# STM32.net
KiCad netlist of a schematic drawn in Altium Designer
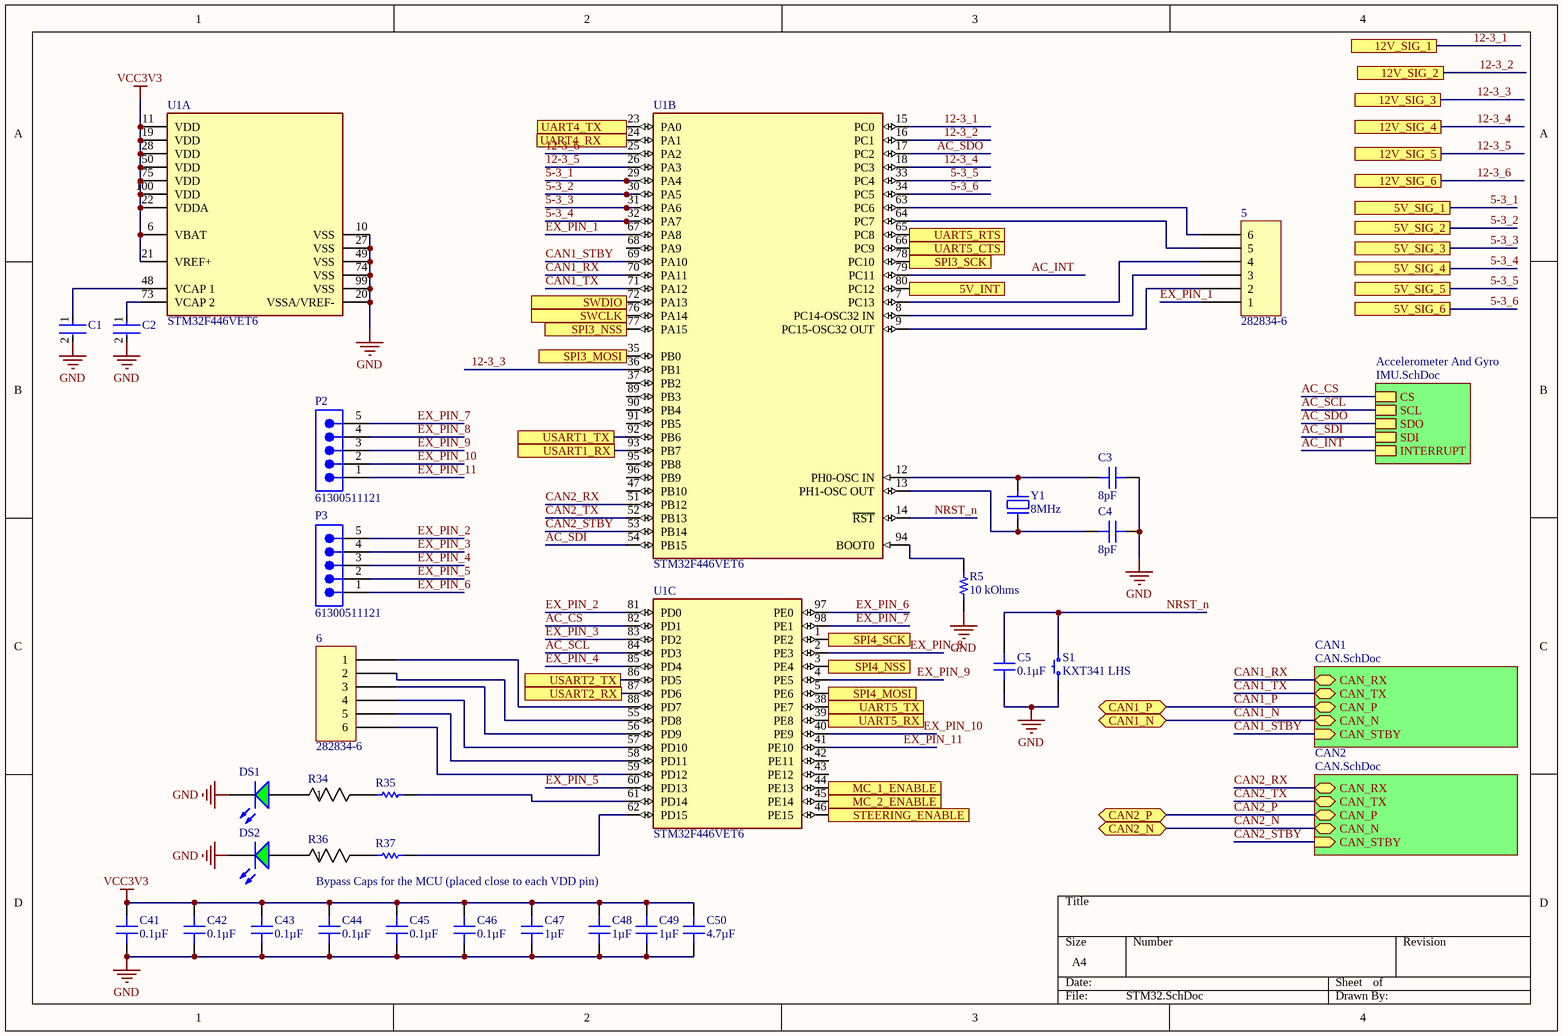
[diagram p0: STM32.SchDoc]

(export (version "E")
  (design (tool "Eeschema 10.0.6"))
  (components
    (comp (ref "5")
      (value "282834-6")
      (footprint "TE 282834-6")
      (description "TERM BLK 6P SIDE ENT 2.54MM PCB")
      (fields (field (name "MANUFACTURER") "TE Connectivity AMP Connectors") (field (name "VOLTAGE") "150V"))
      (libsource (lib "") (part "6 Pin_1"))
    )
    (comp (ref "6")
      (value "282834-6")
      (footprint "TE 282834-6")
      (description "TERM BLK 6P SIDE ENT 2.54MM PCB")
      (fields (field (name "MANUFACTURER") "TE Connectivity AMP Connectors") (field (name "VOLTAGE") "150V"))
      (libsource (lib "Celestial Altium Library - altium_library") (part "6 Pin"))
    )
    (comp (ref "C1")
      (value "GRM188R71A225KE15D")
      (footprint "FP-GRM188-0_1-e0_2_0_5-MFG")
      (description "Chip Multilayer Ceramic Capacitors for General Purpose, 0603, 2.2uF, X7R, 15%, 10%, 10V")
      (fields (field (name "VOLTAGE") "10V") (field (name "TOLERANCE") "10%"))
      (libsource (lib "Altium Content Vault") (part "11868f565c42a9108669ba33697ecf6"))
    )
    (comp (ref "C2")
      (value "GRM188R71A225KE15D")
      (footprint "FP-GRM188-0_1-e0_2_0_5-MFG")
      (description "Chip Multilayer Ceramic Capacitors for General Purpose, 0603, 2.2uF, X7R, 15%, 10%, 10V")
      (fields (field (name "VOLTAGE") "10V") (field (name "TOLERANCE") "10%"))
      (libsource (lib "Altium Content Vault") (part "11868f565c42a9108669ba33697ecf6"))
    )
    (comp (ref "C3")
      (value "8pF")
      (footprint "CAP 0402_1005")
      (description "CAP CER 8PF 50V NP0 0402")
      (fields
        (field (name "PART NUMBER") "C1005NP01H080D050BA")
        (field (name "MANUFACTURER") "TDK Corporation")
      )
      (libsource (lib "Celestial") (part "Capacitor"))
    )
    (comp (ref "C4")
      (value "8pF")
      (footprint "CAP 0402_1005")
      (description "CAP CER 8PF 50V NP0 0402")
      (fields
        (field (name "PART NUMBER") "C1005NP01H080D050BA")
        (field (name "MANUFACTURER") "TDK Corporation")
      )
      (libsource (lib "Celestial") (part "Capacitor"))
    )
    (comp (ref "C5")
      (value "0.1µF")
      (footprint "CAP 0402_1005")
      (description "CAP CER 0402 0.1UF 16V X7R 10%")
      (fields (field (name "PART NUMBER") "C0402C104K4RECAUTO") (field (name "MANUFACTURER") "KEMET"))
      (libsource (lib "CAL") (part "Capacitor"))
    )
    (comp (ref "C41")
      (value "0.1µF")
      (footprint "CAP 0402_1005")
      (description "CAP CER 0402 0.1UF 16V X7R 10%")
      (fields (field (name "PART NUMBER") "C0402C104K4RECAUTO") (field (name "MANUFACTURER") "KEMET"))
      (libsource (lib "CAL") (part "Capacitor"))
    )
    (comp (ref "C42")
      (value "0.1µF")
      (footprint "CAP 0402_1005")
      (description "CAP CER 0402 0.1UF 16V X7R 10%")
      (fields (field (name "PART NUMBER") "C0402C104K4RECAUTO") (field (name "MANUFACTURER") "KEMET"))
      (libsource (lib "CAL") (part "Capacitor"))
    )
    (comp (ref "C43")
      (value "0.1µF")
      (footprint "CAP 0402_1005")
      (description "CAP CER 0402 0.1UF 16V X7R 10%")
      (fields (field (name "PART NUMBER") "C0402C104K4RECAUTO") (field (name "MANUFACTURER") "KEMET"))
      (libsource (lib "CAL") (part "Capacitor"))
    )
    (comp (ref "C44")
      (value "0.1µF")
      (footprint "CAP 0402_1005")
      (description "CAP CER 0402 0.1UF 16V X7R 10%")
      (fields (field (name "PART NUMBER") "C0402C104K4RECAUTO") (field (name "MANUFACTURER") "KEMET"))
      (libsource (lib "CAL") (part "Capacitor"))
    )
    (comp (ref "C45")
      (value "0.1µF")
      (footprint "CAP 0402_1005")
      (description "CAP CER 0402 0.1UF 16V X7R 10%")
      (fields (field (name "PART NUMBER") "C0402C104K4RECAUTO") (field (name "MANUFACTURER") "KEMET"))
      (libsource (lib "CAL") (part "Capacitor"))
    )
    (comp (ref "C46")
      (value "0.1µF")
      (footprint "CAP 0402_1005")
      (description "CAP CER 0402 0.1UF 16V X7R 10%")
      (fields (field (name "PART NUMBER") "C0402C104K4RECAUTO") (field (name "MANUFACTURER") "KEMET"))
      (libsource (lib "CAL") (part "Capacitor"))
    )
    (comp (ref "C47")
      (value "1µF")
      (footprint "CAP 0402_1005")
      (description "CAP CER 1UF 10V X5R 0402")
      (fields
        (field (name "PART NUMBER") "CGB2A1X5R1A105K033BC")
        (field (name "MANUFACTURER") "TDK Corporation")
      )
      (libsource (lib "CAL") (part "Capacitor"))
    )
    (comp (ref "C48")
      (value "1µF")
      (footprint "CAP 0402_1005")
      (description "CAP CER 1UF 10V X5R 0402")
      (fields
        (field (name "PART NUMBER") "CGB2A1X5R1A105K033BC")
        (field (name "MANUFACTURER") "TDK Corporation")
      )
      (libsource (lib "CAL") (part "Capacitor"))
    )
    (comp (ref "C49")
      (value "1µF")
      (footprint "CAP 0402_1005")
      (description "CAP CER 1UF 10V X5R 0402")
      (fields
        (field (name "PART NUMBER") "CGB2A1X5R1A105K033BC")
        (field (name "MANUFACTURER") "TDK Corporation")
      )
      (libsource (lib "CAL") (part "Capacitor"))
    )
    (comp (ref "C50")
      (value "4.7µF")
      (footprint "CAP 0402_1005")
      (description "CAP CER 4.7UF 10V X5R 0402")
      (fields
        (field (name "PART NUMBER") "C1005X5R1A475K050BC")
        (field (name "MANUFACTURER") "TDK Corporation")
      )
      (libsource (lib "CAL") (part "Capacitor"))
    )
    (comp (ref "DS1")
      (value "HLMP-4740")
      (footprint "AVAG-HLMP-4740")
      (description "T-1 3/4 (5 mm) Low Current LED Lamp, Green, 1.9 V, -20 to 100 degC, 2-Pin THD, RoHS, Bulk")
      (fields (field (name "MANUFACTURER") "AvagoTechnologies"))
      (libsource (lib "Altium Content Vault") (part "LED-GREEN-AK-2"))
    )
    (comp (ref "DS2")
      (value "HLMP-4740")
      (footprint "AVAG-HLMP-4740")
      (description "T-1 3/4 (5 mm) Low Current LED Lamp, Green, 1.9 V, -20 to 100 degC, 2-Pin THD, RoHS, Bulk")
      (fields (field (name "MANUFACTURER") "AvagoTechnologies"))
      (libsource (lib "Altium Content Vault") (part "LED-GREEN-AK-2"))
    )
    (comp (ref "P2")
      (value "61300511121")
      (footprint "61300511121")
      (libsource (lib "Altium Content Vault") (part "Header_Male_1R_05P"))
    )
    (comp (ref "P3")
      (value "61300511121")
      (footprint "61300511121")
      (libsource (lib "Altium Content Vault") (part "Header_Male_1R_05P"))
    )
    (comp (ref "R5")
      (value "10 kOhms")
      (footprint "RES 0402_1005")
      (description "RES SMD 10K OHM 0.5% 1/16W 0402")
      (fields (field (name "PART NUMBER") "CRCW040210K0DHEDP") (field (name "MANUFACTURER") "Vishay Dale"))
      (libsource (lib "CAL") (part "Resistor"))
    )
    (comp (ref "R34")
      (value "AC01000005000JA100")
      (footprint "RES_AC01_VIS")
      (fields (field (name "TOLERANCE") "5%"))
      (libsource (lib "Altium Content Vault") (part "AC01000005000JA100"))
    )
    (comp (ref "R35")
      (value "RC0805FR-071KL")
      (footprint "RESC2013X60X35ML10T20")
      (description "Chip Resistor, 1 KOhm, +/- 1%, 125 mW, -55 to 155 degC, 0805 (2012 Metric), RoHS, Tape and Reel")
      (fields (field (name "TOLERANCE") "1%") (field (name "MANUFACTURER") "Yageo"))
      (libsource (lib "Altium Content Vault") (part "RES-2"))
    )
    (comp (ref "R36")
      (value "AC01000005000JA100")
      (footprint "RES_AC01_VIS")
      (fields (field (name "TOLERANCE") "5%"))
      (libsource (lib "Altium Content Vault") (part "AC01000005000JA100"))
    )
    (comp (ref "R37")
      (value "RC0805FR-071KL")
      (footprint "RESC2013X60X35ML10T20")
      (description "Chip Resistor, 1 KOhm, +/- 1%, 125 mW, -55 to 155 degC, 0805 (2012 Metric), RoHS, Tape and Reel")
      (fields (field (name "TOLERANCE") "1%") (field (name "MANUFACTURER") "Yageo"))
      (libsource (lib "Altium Content Vault") (part "RES-2"))
    )
    (comp (ref "S1")
      (value "KXT341 LHS")
      (footprint "C&K KXT3")
      (description "SWITCH TACTILE SPST-NO 0.02A 15V")
      (fields (field (name "MANUFACTURER") "C&K"))
      (libsource (lib "Celestial") (part "SPST-NO 2 PIN"))
    )
    (comp (ref "U1")
      (value "STM32F446VET6")
      (footprint "FP-LQFP100-1L-MFG")
      (description "IC MCU 32BIT 512KB FLASH 100LQFP")
      (fields
        (field (name "OCTOPART") "https://octopart.com/stm32f446vet6-stmicroelectronics-52642922")
        (field (name "MANUFACTURER") "STMicroelectronics")
      )
      (libsource (lib "Altium Content Vault") (part "8e3e88e6cb74ec1f9e49940598abbc7"))
    )
    (comp (ref "Y1")
      (value "8MHz")
      (footprint "NDK NX3225GD")
      (description "CRYSTAL 8.0000MHZ 8PF SMD")
      (fields
        (field (name "PART NUMBER") "NX3225GD-8MHZ-STD-CRA-3")
        (field (name "MANUFACTURER") "NDK America, Inc.")
      )
      (libsource (lib "Celestial") (part "NDK NX3225GD"))
    )
  )
  (nets
    (net (code "1") (name "/5-3_1") (class "Default")
      (node (ref "U1") (pin "29") (pinfunction "PA4_29") (pintype "bidirectional"))
    )
    (net (code "2") (name "/5-3_2") (class "Default")
      (node (ref "U1") (pin "30") (pinfunction "PA5_30") (pintype "bidirectional"))
    )
    (net (code "3") (name "/5-3_3") (class "Default")
      (node (ref "U1") (pin "31") (pinfunction "PA6_31") (pintype "bidirectional"))
    )
    (net (code "4") (name "/5-3_4") (class "Default")
      (node (ref "U1") (pin "32") (pinfunction "PA7_32") (pintype "bidirectional"))
    )
    (net (code "5") (name "/5-3_5") (class "Default")
      (node (ref "U1") (pin "33") (pinfunction "PC4_33") (pintype "bidirectional"))
    )
    (net (code "6") (name "/5-3_6") (class "Default")
      (node (ref "U1") (pin "34") (pinfunction "PC5_34") (pintype "bidirectional"))
    )
    (net (code "7") (name "/5V_INT") (class "Default")
      (node (ref "U1") (pin "80") (pinfunction "PC12_80") (pintype "bidirectional"))
    )
    (net (code "8") (name "/12-3_1") (class "Default")
      (node (ref "U1") (pin "15") (pinfunction "PC0_15") (pintype "bidirectional"))
    )
    (net (code "9") (name "/12-3_2") (class "Default")
      (node (ref "U1") (pin "16") (pinfunction "PC1_16") (pintype "bidirectional"))
    )
    (net (code "10") (name "/12-3_3") (class "Default")
      (node (ref "U1") (pin "36") (pinfunction "PB1_36") (pintype "bidirectional"))
    )
    (net (code "11") (name "/12-3_4") (class "Default")
      (node (ref "U1") (pin "18") (pinfunction "PC3_18") (pintype "bidirectional"))
    )
    (net (code "12") (name "/12-3_5") (class "Default")
      (node (ref "U1") (pin "26") (pinfunction "PA3_26") (pintype "bidirectional"))
    )
    (net (code "13") (name "/12-3_6") (class "Default")
      (node (ref "U1") (pin "25") (pinfunction "PA2_25") (pintype "bidirectional"))
    )
    (net (code "14") (name "/AC_CS") (class "Default")
      (node (ref "U1") (pin "82") (pinfunction "PD1_82") (pintype "bidirectional"))
    )
    (net (code "15") (name "/AC_INT") (class "Default")
      (node (ref "U1") (pin "79") (pinfunction "PC11_79") (pintype "bidirectional"))
    )
    (net (code "16") (name "/AC_SCL") (class "Default")
      (node (ref "U1") (pin "84") (pinfunction "PD3_84") (pintype "bidirectional"))
    )
    (net (code "17") (name "/AC_SDI") (class "Default")
      (node (ref "U1") (pin "54") (pinfunction "PB15_54") (pintype "bidirectional"))
    )
    (net (code "18") (name "/AC_SDO") (class "Default")
      (node (ref "U1") (pin "17") (pinfunction "PC2_17") (pintype "bidirectional"))
    )
    (net (code "21") (name "/CAN1_RX") (class "Default")
      (node (ref "U1") (pin "70") (pinfunction "PA11_70") (pintype "bidirectional"))
    )
    (net (code "22") (name "/CAN1_STBY") (class "Default")
      (node (ref "U1") (pin "69") (pinfunction "PA10_69") (pintype "bidirectional"))
    )
    (net (code "23") (name "/CAN1_TX") (class "Default")
      (node (ref "U1") (pin "71") (pinfunction "PA12_71") (pintype "bidirectional"))
    )
    (net (code "26") (name "/CAN2_RX") (class "Default")
      (node (ref "U1") (pin "51") (pinfunction "PB12_51") (pintype "bidirectional"))
    )
    (net (code "27") (name "/CAN2_STBY") (class "Default")
      (node (ref "U1") (pin "53") (pinfunction "PB14_53") (pintype "bidirectional"))
    )
    (net (code "28") (name "/CAN2_TX") (class "Default")
      (node (ref "U1") (pin "52") (pinfunction "PB13_52") (pintype "bidirectional"))
    )
    (net (code "29") (name "/EX_PIN_1") (class "Default")
      (node (ref "5") (pin "1") (pinfunction "1_1") (pintype "passive"))
      (node (ref "U1") (pin "67") (pinfunction "PA8_67") (pintype "bidirectional"))
    )
    (net (code "30") (name "/EX_PIN_2") (class "Default")
      (node (ref "P3") (pin "5") (pinfunction "5_5") (pintype "passive"))
      (node (ref "U1") (pin "81") (pinfunction "PD0_81") (pintype "bidirectional"))
    )
    (net (code "31") (name "/EX_PIN_3") (class "Default")
      (node (ref "P3") (pin "4") (pinfunction "4_4") (pintype "passive"))
      (node (ref "U1") (pin "83") (pinfunction "PD2_83") (pintype "bidirectional"))
    )
    (net (code "32") (name "/EX_PIN_4") (class "Default")
      (node (ref "P3") (pin "3") (pinfunction "3_3") (pintype "passive"))
      (node (ref "U1") (pin "85") (pinfunction "PD4_85") (pintype "bidirectional"))
    )
    (net (code "33") (name "/EX_PIN_5") (class "Default")
      (node (ref "P3") (pin "2") (pinfunction "2_2") (pintype "passive"))
      (node (ref "U1") (pin "60") (pinfunction "PD13_60") (pintype "bidirectional"))
    )
    (net (code "34") (name "/EX_PIN_6") (class "Default")
      (node (ref "P3") (pin "1") (pinfunction "1_1") (pintype "passive"))
      (node (ref "U1") (pin "97") (pinfunction "PE0_97") (pintype "bidirectional"))
    )
    (net (code "35") (name "/EX_PIN_7") (class "Default")
      (node (ref "P2") (pin "5") (pinfunction "5_5") (pintype "passive"))
      (node (ref "U1") (pin "98") (pinfunction "PE1_98") (pintype "bidirectional"))
    )
    (net (code "36") (name "/EX_PIN_8") (class "Default")
      (node (ref "P2") (pin "4") (pinfunction "4_4") (pintype "passive"))
      (node (ref "U1") (pin "2") (pinfunction "PE3_2") (pintype "bidirectional"))
    )
    (net (code "37") (name "/EX_PIN_9") (class "Default")
      (node (ref "P2") (pin "3") (pinfunction "3_3") (pintype "passive"))
      (node (ref "U1") (pin "4") (pinfunction "PE5_4") (pintype "bidirectional"))
    )
    (net (code "38") (name "/EX_PIN_10") (class "Default")
      (node (ref "P2") (pin "2") (pinfunction "2_2") (pintype "passive"))
      (node (ref "U1") (pin "40") (pinfunction "PE9_40") (pintype "bidirectional"))
    )
    (net (code "39") (name "/EX_PIN_11") (class "Default")
      (node (ref "P2") (pin "1") (pinfunction "1_1") (pintype "passive"))
      (node (ref "U1") (pin "41") (pinfunction "PE10_41") (pintype "bidirectional"))
    )
    (net (code "40") (name "/MC_1_ENABLE") (class "Default")
      (node (ref "U1") (pin "44") (pinfunction "PE13_44") (pintype "bidirectional"))
    )
    (net (code "41") (name "/MC_2_ENABLE") (class "Default")
      (node (ref "U1") (pin "45") (pinfunction "PE14_45") (pintype "bidirectional"))
    )
    (net (code "42") (name "/NRST_n") (class "Default")
      (node (ref "C5") (pin "2") (pinfunction "2_2") (pintype "passive"))
      (node (ref "S1") (pin "2") (pinfunction "2_2") (pintype "passive"))
      (node (ref "U1") (pin "14") (pinfunction "~{RST}_14") (pintype "bidirectional"))
    )
    (net (code "43") (name "/SPI3_MOSI") (class "Default")
      (node (ref "U1") (pin "35") (pinfunction "PB0_35") (pintype "bidirectional"))
    )
    (net (code "44") (name "/SPI3_NSS") (class "Default")
      (node (ref "U1") (pin "77") (pinfunction "PA15_77") (pintype "bidirectional"))
    )
    (net (code "45") (name "/SPI3_SCK") (class "Default")
      (node (ref "U1") (pin "78") (pinfunction "PC10_78") (pintype "bidirectional"))
    )
    (net (code "46") (name "/SPI4_MOSI") (class "Default")
      (node (ref "U1") (pin "5") (pinfunction "PE6_5") (pintype "bidirectional"))
    )
    (net (code "47") (name "/SPI4_NSS") (class "Default")
      (node (ref "U1") (pin "3") (pinfunction "PE4_3") (pintype "bidirectional"))
    )
    (net (code "48") (name "/SPI4_SCK") (class "Default")
      (node (ref "U1") (pin "1") (pinfunction "PE2_1") (pintype "bidirectional"))
    )
    (net (code "49") (name "/STEERING_ENABLE") (class "Default")
      (node (ref "U1") (pin "46") (pinfunction "PE15_46") (pintype "bidirectional"))
    )
    (net (code "50") (name "/SWCLK") (class "Default")
      (node (ref "U1") (pin "76") (pinfunction "PA14_76") (pintype "bidirectional"))
    )
    (net (code "51") (name "/SWDIO") (class "Default")
      (node (ref "U1") (pin "72") (pinfunction "PA13_72") (pintype "bidirectional"))
    )
    (net (code "52") (name "/UART4_RX") (class "Default")
      (node (ref "U1") (pin "24") (pinfunction "PA1_24") (pintype "bidirectional"))
    )
    (net (code "53") (name "/UART4_TX") (class "Default")
      (node (ref "U1") (pin "23") (pinfunction "PA0_23") (pintype "bidirectional"))
    )
    (net (code "54") (name "/UART5_CTS") (class "Default")
      (node (ref "U1") (pin "66") (pinfunction "PC9_66") (pintype "bidirectional"))
    )
    (net (code "55") (name "/UART5_RTS") (class "Default")
      (node (ref "U1") (pin "65") (pinfunction "PC8_65") (pintype "bidirectional"))
    )
    (net (code "56") (name "/UART5_RX") (class "Default")
      (node (ref "U1") (pin "39") (pinfunction "PE8_39") (pintype "bidirectional"))
    )
    (net (code "57") (name "/UART5_TX") (class "Default")
      (node (ref "U1") (pin "38") (pinfunction "PE7_38") (pintype "bidirectional"))
    )
    (net (code "58") (name "/USART1_RX") (class "Default")
      (node (ref "U1") (pin "93") (pinfunction "PB7_93") (pintype "bidirectional"))
    )
    (net (code "59") (name "/USART1_TX") (class "Default")
      (node (ref "U1") (pin "92") (pinfunction "PB6_92") (pintype "bidirectional"))
    )
    (net (code "60") (name "/USART2_RX") (class "Default")
      (node (ref "U1") (pin "87") (pinfunction "PD6_87") (pintype "bidirectional"))
    )
    (net (code "61") (name "/USART2_TX") (class "Default")
      (node (ref "U1") (pin "86") (pinfunction "PD5_86") (pintype "bidirectional"))
    )
    (net (code "62") (name "GND") (class "Default")
      (node (ref "C1") (pin "2") (pinfunction "2_2") (pintype "passive"))
      (node (ref "C2") (pin "2") (pinfunction "2_2") (pintype "passive"))
      (node (ref "C3") (pin "2") (pinfunction "2_2") (pintype "passive"))
      (node (ref "C4") (pin "2") (pinfunction "2_2") (pintype "passive"))
      (node (ref "C41") (pin "1") (pinfunction "1_1") (pintype "passive"))
      (node (ref "C42") (pin "1") (pinfunction "1_1") (pintype "passive"))
      (node (ref "C43") (pin "1") (pinfunction "1_1") (pintype "passive"))
      (node (ref "C44") (pin "1") (pinfunction "1_1") (pintype "passive"))
      (node (ref "C45") (pin "1") (pinfunction "1_1") (pintype "passive"))
      (node (ref "C46") (pin "1") (pinfunction "1_1") (pintype "passive"))
      (node (ref "C47") (pin "1") (pinfunction "1_1") (pintype "passive"))
      (node (ref "C48") (pin "1") (pinfunction "1_1") (pintype "passive"))
      (node (ref "C49") (pin "1") (pinfunction "1_1") (pintype "passive"))
      (node (ref "C5") (pin "1") (pinfunction "1_1") (pintype "passive"))
      (node (ref "C50") (pin "1") (pinfunction "1_1") (pintype "passive"))
      (node (ref "DS1") (pin "2") (pinfunction "K_2") (pintype "passive"))
      (node (ref "DS2") (pin "2") (pinfunction "K_2") (pintype "passive"))
      (node (ref "R5") (pin "1") (pinfunction "1_1") (pintype "passive"))
      (node (ref "S1") (pin "1") (pinfunction "1_1") (pintype "passive"))
      (node (ref "U1") (pin "10") (pinfunction "VSS_10") (pintype "power_in"))
      (node (ref "U1") (pin "20") (pinfunction "VSSA/VREF-_20") (pintype "power_in"))
      (node (ref "U1") (pin "27") (pinfunction "VSS_27") (pintype "power_in"))
      (node (ref "U1") (pin "49") (pinfunction "VSS_49") (pintype "power_in"))
      (node (ref "U1") (pin "74") (pinfunction "VSS_74") (pintype "power_in"))
      (node (ref "U1") (pin "99") (pinfunction "VSS_99") (pintype "power_in"))
    )
    (net (code "63") (name "Net-(DS1-A)") (class "Default")
      (node (ref "DS1") (pin "1") (pinfunction "A_1") (pintype "passive"))
      (node (ref "R34") (pin "1") (pinfunction "1_1") (pintype "passive"))
    )
    (net (code "64") (name "Net-(DS2-A)") (class "Default")
      (node (ref "DS2") (pin "1") (pinfunction "A_1") (pintype "passive"))
      (node (ref "R36") (pin "1") (pinfunction "1_1") (pintype "passive"))
    )
    (net (code "65") (name "Net-(R34-Pad2)") (class "Default")
      (node (ref "R34") (pin "2") (pinfunction "2_2") (pintype "passive"))
      (node (ref "R35") (pin "1") (pinfunction "1_1") (pintype "passive"))
    )
    (net (code "66") (name "Net-(R36-Pad2)") (class "Default")
      (node (ref "R36") (pin "2") (pinfunction "2_2") (pintype "passive"))
      (node (ref "R37") (pin "1") (pinfunction "1_1") (pintype "passive"))
    )
    (net (code "67") (name "Net-(U1A-VCAP_1)") (class "Default")
      (node (ref "C1") (pin "1") (pinfunction "1_1") (pintype "passive"))
      (node (ref "U1") (pin "48") (pinfunction "VCAP_1_48") (pintype "power_in"))
    )
    (net (code "68") (name "Net-(U1A-VCAP_2)") (class "Default")
      (node (ref "C2") (pin "1") (pinfunction "1_1") (pintype "passive"))
      (node (ref "U1") (pin "73") (pinfunction "VCAP_2_73") (pintype "power_in"))
    )
    (net (code "69") (name "Net-(U1B-BOOT0)") (class "Default")
      (node (ref "R5") (pin "2") (pinfunction "2_2") (pintype "passive"))
      (node (ref "U1") (pin "94") (pinfunction "BOOT0_94") (pintype "input"))
    )
    (net (code "70") (name "Net-(U1B-PC6)") (class "Default")
      (node (ref "5") (pin "6") (pinfunction "6_6") (pintype "passive"))
      (node (ref "U1") (pin "63") (pinfunction "PC6_63") (pintype "bidirectional"))
    )
    (net (code "71") (name "Net-(U1B-PC7)") (class "Default")
      (node (ref "5") (pin "5") (pinfunction "5_5") (pintype "passive"))
      (node (ref "U1") (pin "64") (pinfunction "PC7_64") (pintype "bidirectional"))
    )
    (net (code "72") (name "Net-(U1B-PC13)") (class "Default")
      (node (ref "5") (pin "4") (pinfunction "4_4") (pintype "passive"))
      (node (ref "U1") (pin "7") (pinfunction "PC13_7") (pintype "bidirectional"))
    )
    (net (code "73") (name "Net-(U1B-PC14-OSC32_IN)") (class "Default")
      (node (ref "5") (pin "3") (pinfunction "3_3") (pintype "passive"))
      (node (ref "U1") (pin "8") (pinfunction "PC14-OSC32_IN_8") (pintype "bidirectional"))
    )
    (net (code "74") (name "Net-(U1B-PC15-OSC32_OUT)") (class "Default")
      (node (ref "5") (pin "2") (pinfunction "2_2") (pintype "passive"))
      (node (ref "U1") (pin "9") (pinfunction "PC15-OSC32_OUT_9") (pintype "bidirectional"))
    )
    (net (code "75") (name "Net-(U1B-PH0-OSC_IN)") (class "Default")
      (node (ref "C3") (pin "1") (pinfunction "1_1") (pintype "passive"))
      (node (ref "U1") (pin "12") (pinfunction "PH0-OSC_IN_12") (pintype "input"))
      (node (ref "Y1") (pin "2") (pinfunction "2_2") (pintype "passive"))
    )
    (net (code "76") (name "Net-(U1B-PH1-OSC_OUT)") (class "Default")
      (node (ref "C4") (pin "1") (pinfunction "1_1") (pintype "passive"))
      (node (ref "U1") (pin "13") (pinfunction "PH1-OSC_OUT_13") (pintype "bidirectional"))
      (node (ref "Y1") (pin "1") (pinfunction "1_1") (pintype "passive"))
    )
    (net (code "77") (name "Net-(U1C-PD7)") (class "Default")
      (node (ref "6") (pin "1") (pinfunction "1_1") (pintype "passive"))
      (node (ref "U1") (pin "88") (pinfunction "PD7_88") (pintype "bidirectional"))
    )
    (net (code "78") (name "Net-(U1C-PD8)") (class "Default")
      (node (ref "6") (pin "2") (pinfunction "2_2") (pintype "passive"))
      (node (ref "U1") (pin "55") (pinfunction "PD8_55") (pintype "bidirectional"))
    )
    (net (code "79") (name "Net-(U1C-PD9)") (class "Default")
      (node (ref "6") (pin "3") (pinfunction "3_3") (pintype "passive"))
      (node (ref "U1") (pin "56") (pinfunction "PD9_56") (pintype "bidirectional"))
    )
    (net (code "80") (name "Net-(U1C-PD10)") (class "Default")
      (node (ref "6") (pin "4") (pinfunction "4_4") (pintype "passive"))
      (node (ref "U1") (pin "57") (pinfunction "PD10_57") (pintype "bidirectional"))
    )
    (net (code "81") (name "Net-(U1C-PD11)") (class "Default")
      (node (ref "6") (pin "5") (pinfunction "5_5") (pintype "passive"))
      (node (ref "U1") (pin "58") (pinfunction "PD11_58") (pintype "bidirectional"))
    )
    (net (code "82") (name "Net-(U1C-PD12)") (class "Default")
      (node (ref "6") (pin "6") (pinfunction "6_6") (pintype "passive"))
      (node (ref "U1") (pin "59") (pinfunction "PD12_59") (pintype "bidirectional"))
    )
    (net (code "83") (name "Net-(U1C-PD14)") (class "Default")
      (node (ref "R35") (pin "2") (pinfunction "2_2") (pintype "passive"))
      (node (ref "U1") (pin "61") (pinfunction "PD14_61") (pintype "bidirectional"))
    )
    (net (code "84") (name "Net-(U1C-PD15)") (class "Default")
      (node (ref "R37") (pin "2") (pinfunction "2_2") (pintype "passive"))
      (node (ref "U1") (pin "62") (pinfunction "PD15_62") (pintype "bidirectional"))
    )
    (net (code "85") (name "VCC3V3") (class "Default")
      (node (ref "C41") (pin "2") (pinfunction "2_2") (pintype "passive"))
      (node (ref "C42") (pin "2") (pinfunction "2_2") (pintype "passive"))
      (node (ref "C43") (pin "2") (pinfunction "2_2") (pintype "passive"))
      (node (ref "C44") (pin "2") (pinfunction "2_2") (pintype "passive"))
      (node (ref "C45") (pin "2") (pinfunction "2_2") (pintype "passive"))
      (node (ref "C46") (pin "2") (pinfunction "2_2") (pintype "passive"))
      (node (ref "C47") (pin "2") (pinfunction "2_2") (pintype "passive"))
      (node (ref "C48") (pin "2") (pinfunction "2_2") (pintype "passive"))
      (node (ref "C49") (pin "2") (pinfunction "2_2") (pintype "passive"))
      (node (ref "C50") (pin "2") (pinfunction "2_2") (pintype "passive"))
      (node (ref "U1") (pin "100") (pinfunction "VDD_100") (pintype "power_in"))
      (node (ref "U1") (pin "11") (pinfunction "VDD_11") (pintype "power_in"))
      (node (ref "U1") (pin "19") (pinfunction "VDD_19") (pintype "power_in"))
      (node (ref "U1") (pin "21") (pinfunction "VREF+_21") (pintype "power_in"))
      (node (ref "U1") (pin "22") (pinfunction "VDDA_22") (pintype "power_in"))
      (node (ref "U1") (pin "28") (pinfunction "VDD_28") (pintype "power_in"))
      (node (ref "U1") (pin "50") (pinfunction "VDD_50") (pintype "power_in"))
      (node (ref "U1") (pin "6") (pinfunction "VBAT_6") (pintype "power_in"))
      (node (ref "U1") (pin "75") (pinfunction "VDD_75") (pintype "power_in"))
    )
    (net (code "86") (name "unconnected-(U1B-PA9-Pad68)") (class "Default")
      (node (ref "U1") (pin "68") (pinfunction "PA9_68") (pintype "bidirectional"))
    )
    (net (code "87") (name "unconnected-(U1B-PB2-Pad37)") (class "Default")
      (node (ref "U1") (pin "37") (pinfunction "PB2_37") (pintype "bidirectional"))
    )
    (net (code "88") (name "unconnected-(U1B-PB3-Pad89)") (class "Default")
      (node (ref "U1") (pin "89") (pinfunction "PB3_89") (pintype "bidirectional"))
    )
    (net (code "89") (name "unconnected-(U1B-PB4-Pad90)") (class "Default")
      (node (ref "U1") (pin "90") (pinfunction "PB4_90") (pintype "bidirectional"))
    )
    (net (code "90") (name "unconnected-(U1B-PB5-Pad91)") (class "Default")
      (node (ref "U1") (pin "91") (pinfunction "PB5_91") (pintype "bidirectional"))
    )
    (net (code "91") (name "unconnected-(U1B-PB8-Pad95)") (class "Default")
      (node (ref "U1") (pin "95") (pinfunction "PB8_95") (pintype "bidirectional"))
    )
    (net (code "92") (name "unconnected-(U1B-PB9-Pad96)") (class "Default")
      (node (ref "U1") (pin "96") (pinfunction "PB9_96") (pintype "bidirectional"))
    )
    (net (code "93") (name "unconnected-(U1B-PB10-Pad47)") (class "Default")
      (node (ref "U1") (pin "47") (pinfunction "PB10_47") (pintype "bidirectional"))
    )
    (net (code "94") (name "unconnected-(U1C-PE11-Pad42)") (class "Default")
      (node (ref "U1") (pin "42") (pinfunction "PE11_42") (pintype "bidirectional"))
    )
    (net (code "95") (name "unconnected-(U1C-PE12-Pad43)") (class "Default")
      (node (ref "U1") (pin "43") (pinfunction "PE12_43") (pintype "bidirectional"))
    )
  )
)
